# F1C200S.net
KiCad netlist of a schematic drawn in Altium Designer
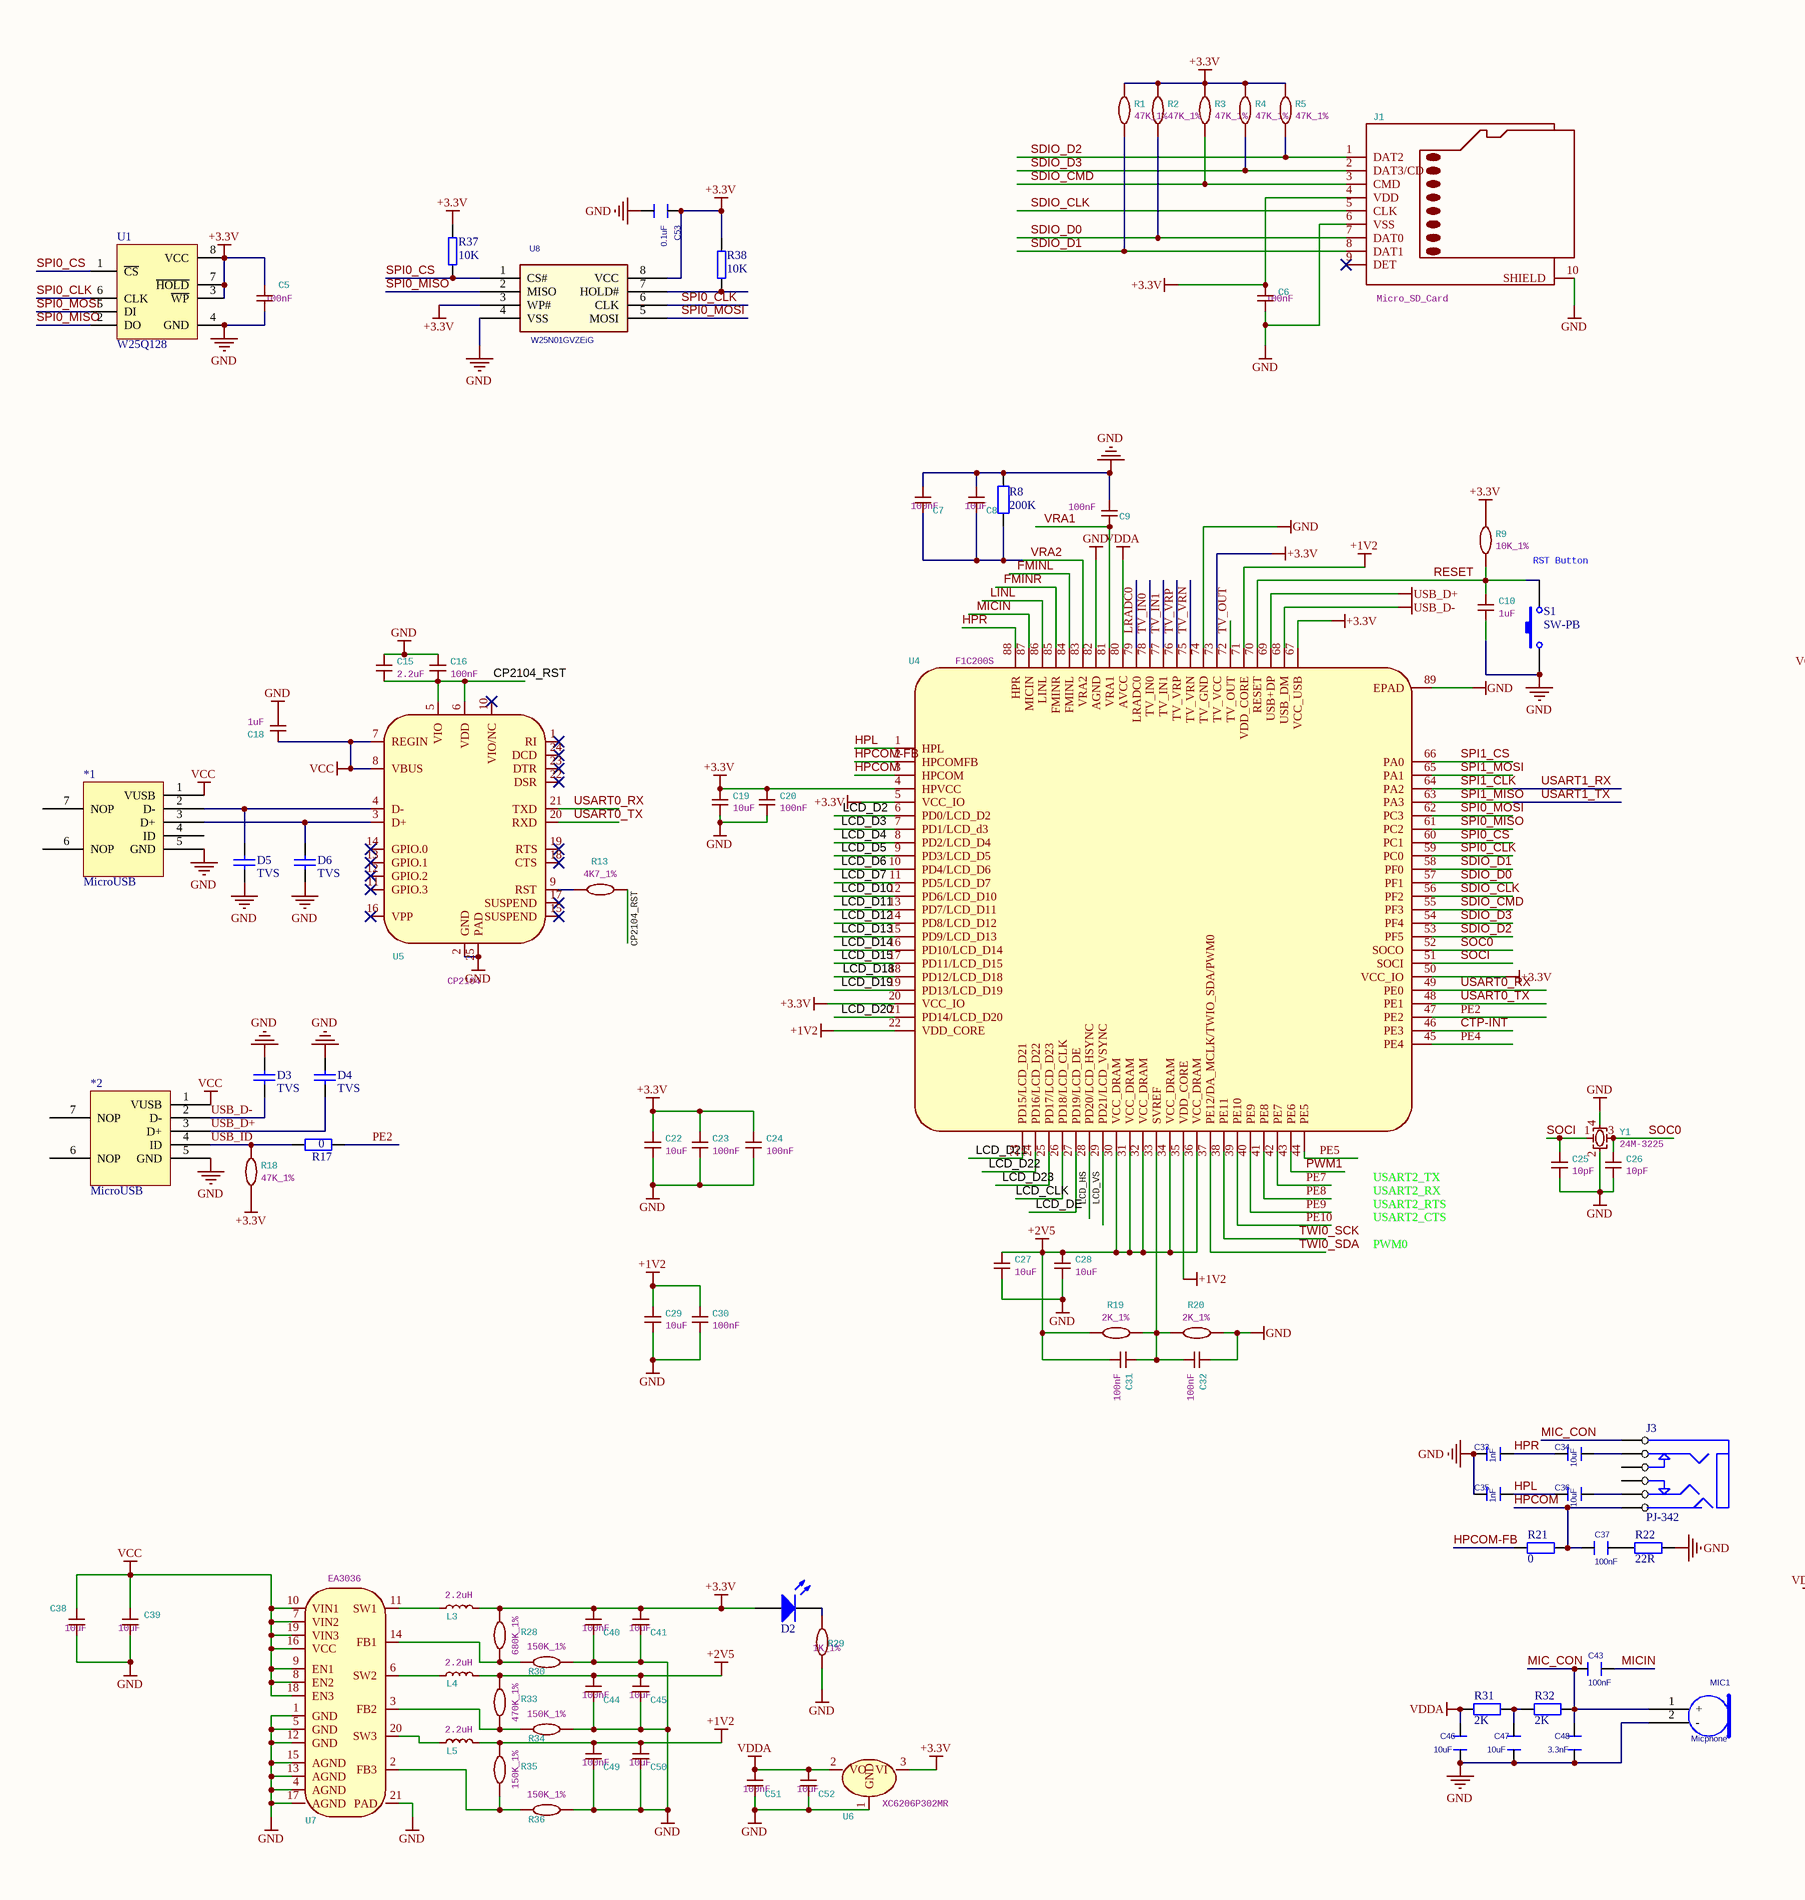
[diagram p0: F1C200S.SchDoc, left]
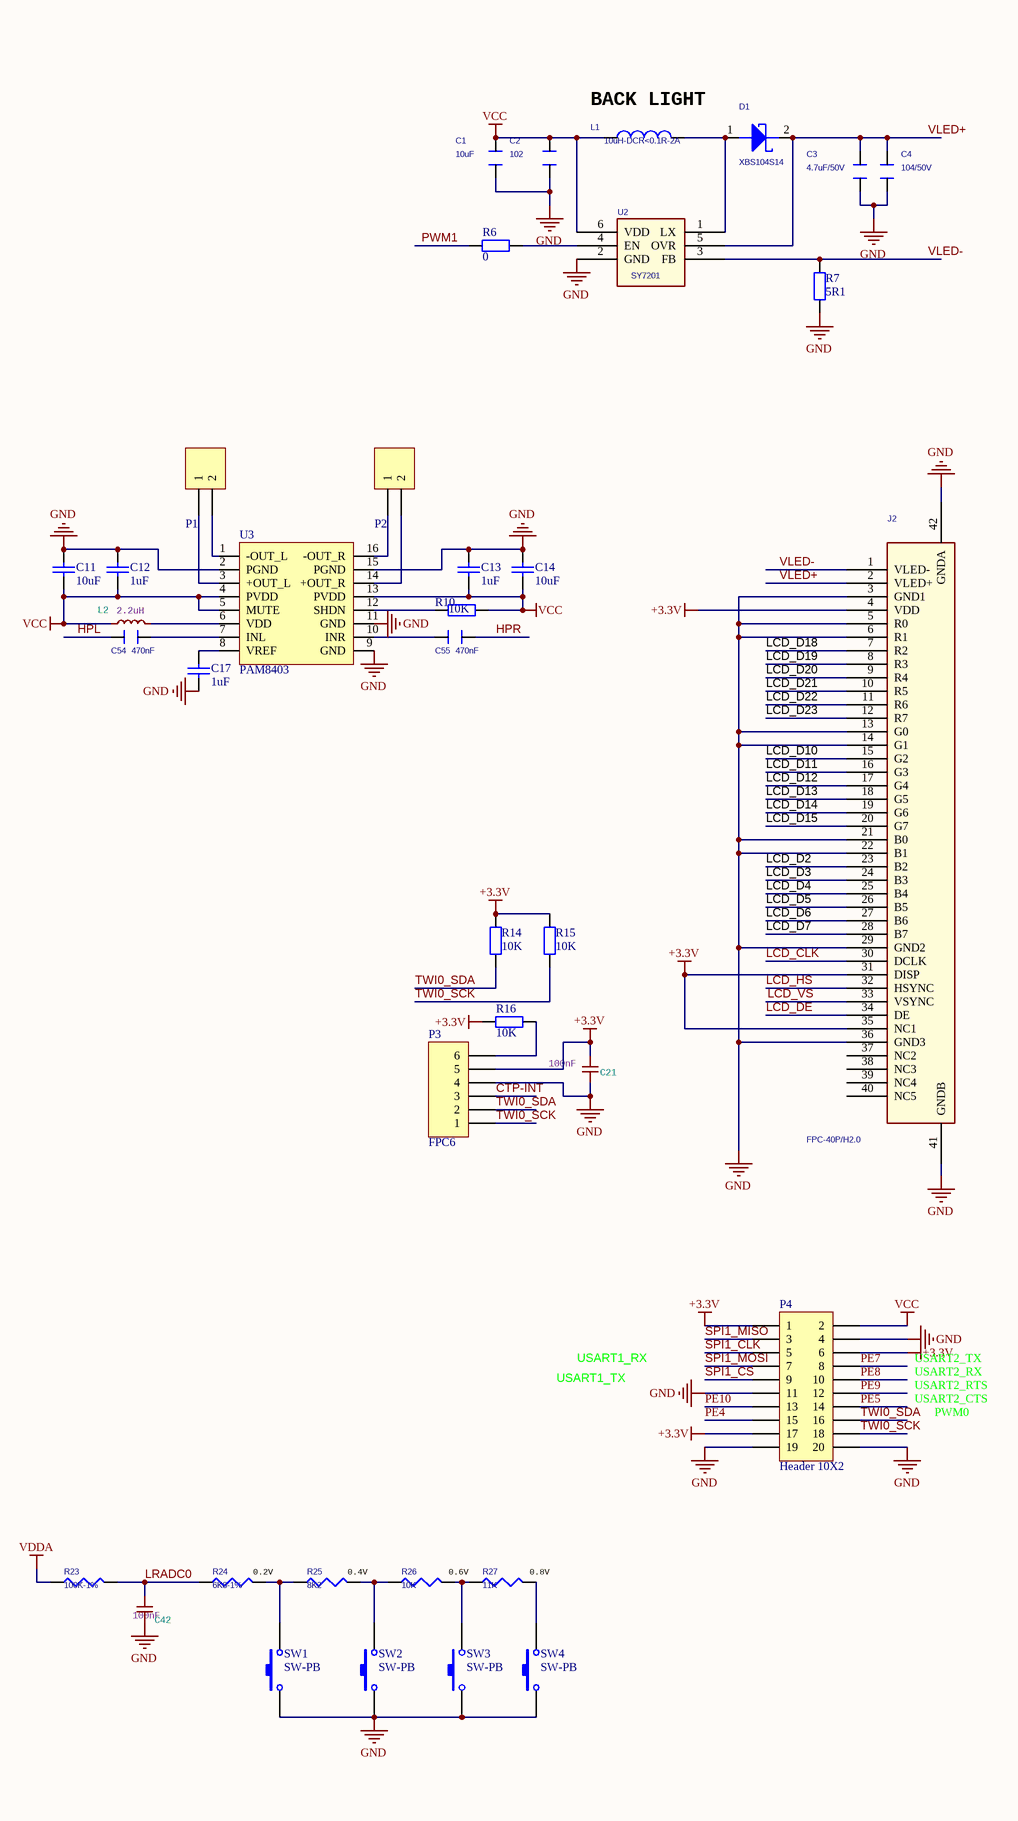
[diagram p1: F1C200S.SchDoc, right]

(export (version "E")
  (design (tool "Eeschema 10.0.6"))
  (components
    (comp (ref "*1")
      (value "MicroUSB")
      (footprint "USB_Micro - 4FP")
      (libsource (lib "USB") (part "MicroUSB"))
    )
    (comp (ref "*2")
      (value "MicroUSB")
      (footprint "USB_Micro - 4FP")
      (libsource (lib "USB") (part "MicroUSB"))
    )
    (comp (ref "C1") (value "10uF") (footprint "C0603") (libsource (lib "*") (part "CAPACITOR_0_Dup5")))
    (comp (ref "C2") (value "102") (footprint "C0603") (libsource (lib "*") (part "CAPACITOR_0_Dup5")))
    (comp (ref "C3") (value "4.7uF/50V") (footprint "C0603") (libsource (lib "*") (part "CAPACITOR_0_Dup5")))
    (comp (ref "C4") (value "104/50V") (footprint "C0603") (libsource (lib "*") (part "CAPACITOR_0_Dup5")))
    (comp (ref "C5")
      (value "03.0009_C0402_100nF")
      (footprint "C0402")
      (libsource (lib "altium-import") (part "root_0_03.0009_C0402_100nF_"))
    )
    (comp (ref "C6")
      (value "03.0009_C0402_100nF")
      (footprint "C0402")
      (libsource (lib "altium-import") (part "root_0_03.0009_C0402_100nF_"))
    )
    (comp (ref "C7")
      (value "03.0009_C0402_100nF")
      (footprint "C0402")
      (libsource (lib "altium-import") (part "root_0_mirrored_03.0009_C0402_100nF_"))
    )
    (comp (ref "C8")
      (value "03.4004_C0603_10uF")
      (footprint "C0603")
      (libsource (lib "altium-import") (part "root_0_mirrored_03.4004_C0603_10uF_"))
    )
    (comp (ref "C9")
      (value "03.0009_C0402_100nF")
      (footprint "C0402")
      (libsource (lib "altium-import") (part "root_3_03.0009_C0402_100nF_"))
    )
    (comp (ref "C10")
      (value "03.0001_C0402_1uF")
      (footprint "C0402")
      (libsource (lib "altium-import") (part "root_0_03.0001_C0402_1uF_"))
    )
    (comp (ref "C11")
      (value "10uF")
      (footprint "C0603")
      (description "无极性电容")
      (fields (field (name "Comment") "Cap") (field (name "PUBLISHER") "Altium Limited"))
      (libsource (lib "fszhang") (part "Cap"))
    )
    (comp (ref "C12")
      (value "1uF")
      (footprint "C0402")
      (description "无极性电容")
      (fields (field (name "Comment") "Cap") (field (name "PUBLISHER") "Altium Limited"))
      (libsource (lib "fszhang") (part "Cap"))
    )
    (comp (ref "C13")
      (value "1uF")
      (footprint "C0402")
      (description "无极性电容")
      (fields (field (name "Comment") "Cap") (field (name "PUBLISHER") "Altium Limited"))
      (libsource (lib "fszhang") (part "Cap"))
    )
    (comp (ref "C14")
      (value "10uF")
      (footprint "C0603")
      (description "无极性电容")
      (fields (field (name "Comment") "Cap") (field (name "PUBLISHER") "Altium Limited"))
      (libsource (lib "fszhang") (part "Cap"))
    )
    (comp (ref "C15")
      (value "03.4002_C0603_2.2uF")
      (footprint "C0402")
      (libsource (lib "altium-import") (part "root_0_03.4002_C0603_2.2uF_"))
    )
    (comp (ref "C16")
      (value "03.0009_C0402_100nF")
      (footprint "C0402")
      (libsource (lib "altium-import") (part "root_0_03.0009_C0402_100nF_"))
    )
    (comp (ref "C17")
      (value "1uF")
      (footprint "C0402")
      (description "无极性电容")
      (fields (field (name "Comment") "Cap") (field (name "PUBLISHER") "Altium Limited"))
      (libsource (lib "fszhang") (part "Cap"))
    )
    (comp (ref "C18")
      (value "03.4001_C0603_1uF")
      (footprint "C0402")
      (libsource (lib "altium-import") (part "root_0_03.4001_C0603_1uF_"))
    )
    (comp (ref "C19")
      (value "03.4004_C0603_10uF")
      (footprint "C0603")
      (libsource (lib "altium-import") (part "root_0_03.4004_C0603_10uF_"))
    )
    (comp (ref "C20")
      (value "03.0009_C0402_100nF")
      (footprint "C0402")
      (libsource (lib "altium-import") (part "root_0_03.0009_C0402_100nF_"))
    )
    (comp (ref "C21")
      (value "03.0009_C0402_100nF")
      (footprint "C0402")
      (libsource (lib "altium-import") (part "root_3_03.0009_C0402_100nF_"))
    )
    (comp (ref "C22")
      (value "03.4004_C0603_10uF")
      (footprint "C0603")
      (libsource (lib "altium-import") (part "root_0_03.4004_C0603_10uF_"))
    )
    (comp (ref "C23")
      (value "03.0009_C0402_100nF")
      (footprint "C0402")
      (libsource (lib "altium-import") (part "root_0_03.0009_C0402_100nF_"))
    )
    (comp (ref "C24")
      (value "03.0009_C0402_100nF")
      (footprint "C0402")
      (libsource (lib "altium-import") (part "root_0_03.0009_C0402_100nF_"))
    )
    (comp (ref "C25")
      (value "03.0003_C0402_10pF")
      (footprint "C0402")
      (libsource (lib "altium-import") (part "root_0_03.0003_C0402_10pF_"))
    )
    (comp (ref "C26")
      (value "03.0003_C0402_10pF")
      (footprint "C0402")
      (libsource (lib "altium-import") (part "root_0_03.0003_C0402_10pF_"))
    )
    (comp (ref "C27")
      (value "03.4004_C0603_10uF")
      (footprint "C0603")
      (libsource (lib "altium-import") (part "root_0_03.4004_C0603_10uF_"))
    )
    (comp (ref "C28")
      (value "03.4004_C0603_10uF")
      (footprint "C0603")
      (libsource (lib "altium-import") (part "root_0_03.4004_C0603_10uF_"))
    )
    (comp (ref "C29")
      (value "03.4004_C0603_10uF")
      (footprint "C0603")
      (libsource (lib "altium-import") (part "root_0_03.4004_C0603_10uF_"))
    )
    (comp (ref "C30")
      (value "03.0009_C0402_100nF")
      (footprint "C0402")
      (libsource (lib "altium-import") (part "root_0_03.0009_C0402_100nF_"))
    )
    (comp (ref "C31")
      (value "03.0009_C0402_100nF")
      (footprint "C0402")
      (libsource (lib "") (part "root_0_03.0009_C0402_100nF__1"))
    )
    (comp (ref "C32")
      (value "03.0009_C0402_100nF")
      (footprint "C0402")
      (libsource (lib "") (part "root_0_03.0009_C0402_100nF__1"))
    )
    (comp (ref "C33") (value "1nF") (footprint "C0402") (libsource (lib "*") (part "CAPACITOR_Dup3")))
    (comp (ref "C34") (value "10uF") (footprint "C0603") (libsource (lib "*") (part "CAPACITOR_Dup3")))
    (comp (ref "C35") (value "1nF") (footprint "C0402") (libsource (lib "*") (part "CAPACITOR_Dup3")))
    (comp (ref "C36") (value "10uF") (footprint "C0603") (libsource (lib "*") (part "CAPACITOR_Dup3")))
    (comp (ref "C37") (value "100nF") (footprint "C0402") (libsource (lib "*") (part "CAPACITOR_Dup3")))
    (comp (ref "C38")
      (value "03.4004_C0603_10uF")
      (footprint "C0603")
      (libsource (lib "altium-import") (part "root_0_mirrored_03.4004_C0603_10uF_"))
    )
    (comp (ref "C39")
      (value "03.4004_C0603_10uF")
      (footprint "C0603")
      (libsource (lib "altium-import") (part "root_0_mirrored_03.4004_C0603_10uF_"))
    )
    (comp (ref "C40")
      (value "03.0009_C0402_100nF")
      (footprint "C0402")
      (libsource (lib "altium-import") (part "root_0_mirrored_03.0009_C0402_100nF_"))
    )
    (comp (ref "C41")
      (value "03.4004_C0603_10uF")
      (footprint "C0603")
      (libsource (lib "altium-import") (part "root_0_mirrored_03.4004_C0603_10uF_"))
    )
    (comp (ref "C42")
      (value "03.0009_C0402_100nF")
      (footprint "C0402")
      (libsource (lib "altium-import") (part "root_0_mirrored_03.0009_C0402_100nF_"))
    )
    (comp (ref "C43") (value "100nF") (footprint "C0402") (libsource (lib "*") (part "CAPACITOR_Dup3")))
    (comp (ref "C44")
      (value "03.0009_C0402_100nF")
      (footprint "C0402")
      (libsource (lib "altium-import") (part "root_0_mirrored_03.0009_C0402_100nF_"))
    )
    (comp (ref "C45")
      (value "03.4004_C0603_10uF")
      (footprint "C0603")
      (libsource (lib "altium-import") (part "root_0_mirrored_03.4004_C0603_10uF_"))
    )
    (comp (ref "C46") (value "10uF") (footprint "C0603") (libsource (lib "*") (part "CAPACITOR_Dup3")))
    (comp (ref "C47") (value "10uF") (footprint "C0603") (libsource (lib "*") (part "CAPACITOR_Dup3")))
    (comp (ref "C48") (value "3.3nF") (footprint "C0402") (libsource (lib "*") (part "CAPACITOR_Dup3")))
    (comp (ref "C49")
      (value "03.0009_C0402_100nF")
      (footprint "C0402")
      (libsource (lib "altium-import") (part "root_0_mirrored_03.0009_C0402_100nF_"))
    )
    (comp (ref "C50")
      (value "03.4004_C0603_10uF")
      (footprint "C0603")
      (libsource (lib "altium-import") (part "root_0_mirrored_03.4004_C0603_10uF_"))
    )
    (comp (ref "C51")
      (value "03.0009_C0402_100nF")
      (footprint "C0402")
      (libsource (lib "altium-import") (part "root_0_mirrored_03.0009_C0402_100nF_"))
    )
    (comp (ref "C52")
      (value "03.4004_C0603_10uF")
      (footprint "C0603")
      (libsource (lib "altium-import") (part "root_0_mirrored_03.4004_C0603_10uF_"))
    )
    (comp (ref "C53") (value "0.1uF") (footprint "C0402") (libsource (lib "*") (part "CAPACITOR_Dup1")))
    (comp (ref "C54") (value "470nF") (footprint "C0402") (libsource (lib "*") (part "CAPACITOR_Dup1")))
    (comp (ref "C55") (value "470nF") (footprint "C0402") (libsource (lib "*") (part "CAPACITOR_Dup1")))
    (comp (ref "D1")
      (value "XBS104S14")
      (footprint "SOD123")
      (description "RoHS 1.0 Ampere Schottky Barrier Rectifiers  SOD-123")
      (libsource (lib "*") (part "DIODE SCHOTTKY_0"))
    )
    (comp (ref "D2")
      (value "LED0")
      (footprint "0603LED")
      (description "发光二极管")
      (fields (field (name "PUBLISHER") "Altium Limited"))
      (libsource (lib "fszhang") (part "LED0"))
    )
    (comp (ref "D3")
      (value "TVS")
      (footprint "C0402")
      (description "无极性电容")
      (fields (field (name "Comment") "Cap") (field (name "PUBLISHER") "Altium Limited"))
      (libsource (lib "fszhang") (part "Cap"))
    )
    (comp (ref "D4")
      (value "TVS")
      (footprint "C0402")
      (description "无极性电容")
      (fields (field (name "Comment") "Cap") (field (name "PUBLISHER") "Altium Limited"))
      (libsource (lib "fszhang") (part "Cap"))
    )
    (comp (ref "D5")
      (value "TVS")
      (footprint "C0402")
      (description "无极性电容")
      (fields (field (name "Comment") "Cap") (field (name "PUBLISHER") "Altium Limited"))
      (libsource (lib "fszhang") (part "Cap"))
    )
    (comp (ref "D6")
      (value "TVS")
      (footprint "C0402")
      (description "无极性电容")
      (fields (field (name "Comment") "Cap") (field (name "PUBLISHER") "Altium Limited"))
      (libsource (lib "fszhang") (part "Cap"))
    )
    (comp (ref "J1")
      (value "10.0001_Micro_SD_Card")
      (footprint "SDCARD-M")
      (libsource (lib "altium-import") (part "root_0_10.0001_Micro_SD_Card_"))
    )
    (comp (ref "J2")
      (value "FPC-40P/H2.0")
      (footprint "FPC0.5-40P-B")
      (libsource (lib "*") (part "LCD-LW500AC9001_0"))
    )
    (comp (ref "J3") (value "PJ-342") (footprint "PJ-342") (libsource (lib "lpi-nano-dock") (part "PJ-342")))
    (comp (ref "L1")
      (value "10uH-DCR<0.1R-2A")
      (footprint "3015")
      (description "RoHS Power Inductor 22uH 300mA H<1.8MM,CD32")
      (libsource (lib "*") (part "INDUCTOR_3"))
    )
    (comp (ref "L2")
      (value "06.0102_L2520_2.2uH")
      (footprint "3015")
      (libsource (lib "altium-import") (part "root_0_mirrored_06.0102_L2520_2.2uH_"))
    )
    (comp (ref "L3")
      (value "06.0102_L2520_2.2uH")
      (footprint "3015")
      (libsource (lib "altium-import") (part "root_0_mirrored_06.0102_L2520_2.2uH_"))
    )
    (comp (ref "L4")
      (value "06.0102_L2520_2.2uH")
      (footprint "3015")
      (libsource (lib "altium-import") (part "root_0_mirrored_06.0102_L2520_2.2uH_"))
    )
    (comp (ref "L5")
      (value "06.0102_L2520_2.2uH")
      (footprint "3015")
      (libsource (lib "altium-import") (part "root_0_mirrored_06.0102_L2520_2.2uH_"))
    )
    (comp (ref "MIC1") (value "Micphone") (footprint "MIC_6022") (libsource (lib "*") (part "Micphone_0")))
    (comp (ref "P1")
      (value "Header 2")
      (footprint "HDR2X1_A")
      (description "接插件")
      (fields (field (name "PUBLISHER") "Altium Limited"))
      (libsource (lib "fszhang") (part "Header 2"))
    )
    (comp (ref "P2")
      (value "Header 2")
      (footprint "HDR2X1_A")
      (description "接插件")
      (fields (field (name "PUBLISHER") "Altium Limited"))
      (libsource (lib "fszhang") (part "Header 2"))
    )
    (comp (ref "P3")
      (value "FPC6")
      (footprint "FPC0.5-6P-A")
      (description "接插件")
      (fields (field (name "PUBLISHER") "Altium Limited"))
      (libsource (lib "fszhang") (part "Header 6"))
    )
    (comp (ref "P4")
      (value "Header 10X2")
      (footprint "HDR2X10")
      (description "Header, 10-Pin, Dual row")
      (fields (field (name "PUBLISHER") "Altium Limited"))
      (libsource (lib "Miscellaneous Connectors") (part "Header 10X2"))
    )
    (comp (ref "R1")
      (value "02.0014_R0402_10K_1%")
      (footprint "R0402")
      (libsource (lib "altium-import") (part "root_0_02.0014_R0402_47K_1%_"))
    )
    (comp (ref "R2")
      (value "02.0014_R0402_10K_1%")
      (footprint "R0402")
      (libsource (lib "altium-import") (part "root_0_02.0014_R0402_47K_1%_"))
    )
    (comp (ref "R3")
      (value "02.0014_R0402_10K_1%")
      (footprint "R0402")
      (libsource (lib "altium-import") (part "root_0_02.0014_R0402_47K_1%_"))
    )
    (comp (ref "R4")
      (value "02.0014_R0402_10K_1%")
      (footprint "R0402")
      (libsource (lib "altium-import") (part "root_0_02.0014_R0402_47K_1%_"))
    )
    (comp (ref "R5")
      (value "02.0014_R0402_10K_1%")
      (footprint "R0402")
      (libsource (lib "altium-import") (part "root_0_02.0014_R0402_47K_1%_"))
    )
    (comp (ref "R6")
      (value "0")
      (footprint "R0402")
      (description "贴片电阻")
      (fields (field (name "Comment") "Res1") (field (name "PUBLISHER") "Altium Limited"))
      (libsource (lib "") (part "Res1_1"))
    )
    (comp (ref "R7")
      (value "5R1")
      (footprint "R0603")
      (description "贴片电阻")
      (fields (field (name "Comment") "Res1") (field (name "PUBLISHER") "Altium Limited"))
      (libsource (lib "") (part "Res1_2"))
    )
    (comp (ref "R8")
      (value "200K")
      (footprint "R0402")
      (description "贴片电阻")
      (fields (field (name "Comment") "Res1") (field (name "PUBLISHER") "Altium Limited"))
      (libsource (lib "fszhang") (part "Res1"))
    )
    (comp (ref "R9")
      (value "02.0008_R0402_10K_1%")
      (footprint "R0402")
      (libsource (lib "altium-import") (part "root_0_02.0008_R0402_10K_1%_"))
    )
    (comp (ref "R10")
      (value "10K")
      (footprint "R0402")
      (description "贴片电阻")
      (fields (field (name "Comment") "Res1") (field (name "PUBLISHER") "Altium Limited"))
      (libsource (lib "fszhang") (part "Res1"))
    )
    (comp (ref "R13")
      (value "02.0005_R0402_4K7_1%")
      (footprint "R0402")
      (libsource (lib "altium-import") (part "root_0_02.0005_R0402_4K7_1%_"))
    )
    (comp (ref "R14")
      (value "10K")
      (footprint "R0402")
      (description "贴片电阻")
      (fields (field (name "Comment") "Res1") (field (name "PUBLISHER") "Altium Limited"))
      (libsource (lib "") (part "Res1_1"))
    )
    (comp (ref "R15")
      (value "10K")
      (footprint "R0402")
      (description "贴片电阻")
      (fields (field (name "Comment") "Res1") (field (name "PUBLISHER") "Altium Limited"))
      (libsource (lib "") (part "Res1_1"))
    )
    (comp (ref "R16")
      (value "10K")
      (footprint "R0402")
      (description "贴片电阻")
      (fields (field (name "Comment") "Res1") (field (name "PUBLISHER") "Altium Limited"))
      (libsource (lib "") (part "Res1_2"))
    )
    (comp (ref "R17")
      (value "0")
      (footprint "R0402")
      (description "贴片电阻")
      (fields (field (name "Comment") "Res1") (field (name "PUBLISHER") "Altium Limited"))
      (libsource (lib "") (part "Res1_1"))
    )
    (comp (ref "R18")
      (value "02.0014_R0402_10K_1%")
      (footprint "R0402")
      (libsource (lib "altium-import") (part "root_0_02.0014_R0402_47K_1%_"))
    )
    (comp (ref "R19")
      (value "02.0026_R0402_2K_1%")
      (footprint "R0402")
      (libsource (lib "altium-import") (part "root_0_02.0026_R0402_2K_1%_"))
    )
    (comp (ref "R20")
      (value "02.0026_R0402_2K_1%")
      (footprint "R0402")
      (libsource (lib "altium-import") (part "root_0_02.0026_R0402_2K_1%_"))
    )
    (comp (ref "R21")
      (value "0")
      (footprint "R0402")
      (description "贴片电阻")
      (fields (field (name "Comment") "Res1") (field (name "PUBLISHER") "Altium Limited"))
      (libsource (lib "") (part "Res1_3"))
    )
    (comp (ref "R22")
      (value "22R")
      (footprint "R0603")
      (description "贴片电阻")
      (fields (field (name "Comment") "Res1") (field (name "PUBLISHER") "Altium Limited"))
      (libsource (lib "") (part "Res1_3"))
    )
    (comp (ref "R23") (value "100K-1%") (footprint "R0402") (libsource (lib "*") (part "R1 0805_Dup1")))
    (comp (ref "R24") (value "6K8-1%") (footprint "R0402") (libsource (lib "*") (part "R1 0805_Dup1")))
    (comp (ref "R25") (value "8K2") (footprint "R0402") (libsource (lib "*") (part "R1 0805_Dup1")))
    (comp (ref "R26") (value "10K") (footprint "R0402") (libsource (lib "*") (part "R1 0805_Dup1")))
    (comp (ref "R27") (value "11K") (footprint "R0402") (libsource (lib "*") (part "R1 0805_Dup1")))
    (comp (ref "R28")
      (value "02.0025_R0402_680K_1%")
      (footprint "R0402")
      (libsource (lib "altium-import") (part "root_0_mirrored_02.0025_R0402_680K_1%_"))
    )
    (comp (ref "R29")
      (value "02.0003_R0402_1K_1%")
      (footprint "R0402")
      (libsource (lib "altium-import") (part "root_0_mirrored_02.0003_R0402_1K_1%_"))
    )
    (comp (ref "R30")
      (value "02.0023_R0402_150K_1%")
      (footprint "R0402")
      (libsource (lib "altium-import") (part "root_0_mirrored_02.0023_R0402_150K_1%_"))
    )
    (comp (ref "R31")
      (value "2K")
      (footprint "R0402")
      (description "贴片电阻")
      (fields (field (name "Comment") "Res1") (field (name "PUBLISHER") "Altium Limited"))
      (libsource (lib "") (part "Res1_3"))
    )
    (comp (ref "R32")
      (value "2K")
      (footprint "R0402")
      (description "贴片电阻")
      (fields (field (name "Comment") "Res1") (field (name "PUBLISHER") "Altium Limited"))
      (libsource (lib "") (part "Res1_3"))
    )
    (comp (ref "R33")
      (value "02.0024_R0402_470K_1%")
      (footprint "R0402")
      (libsource (lib "altium-import") (part "root_0_mirrored_02.0024_R0402_470K_1%_"))
    )
    (comp (ref "R34")
      (value "02.0023_R0402_150K_1%")
      (footprint "R0402")
      (libsource (lib "altium-import") (part "root_0_mirrored_02.0023_R0402_150K_1%_"))
    )
    (comp (ref "R35")
      (value "02.0023_R0402_150K_1%")
      (footprint "R0402")
      (libsource (lib "") (part "root_0_mirrored_02.0023_R0402_150K_1%__1"))
    )
    (comp (ref "R36")
      (value "02.0023_R0402_150K_1%")
      (footprint "R0402")
      (libsource (lib "altium-import") (part "root_0_mirrored_02.0023_R0402_150K_1%_"))
    )
    (comp (ref "R37")
      (value "10K")
      (footprint "R0402")
      (description "Resistor")
      (libsource (lib "Renhaibo") (part "电阻Ω"))
    )
    (comp (ref "R38")
      (value "10K")
      (footprint "R0402")
      (description "Resistor")
      (libsource (lib "Renhaibo") (part "电阻Ω"))
    )
    (comp (ref "S1")
      (value "SW-PB")
      (footprint "SW_PB4_3*4*2.5")
      (description "微动开关")
      (fields (field (name "PUBLISHER") "Altium Limited"))
      (libsource (lib "fszhang") (part "SW-PB"))
    )
    (comp (ref "SW1")
      (value "SW-PB")
      (footprint "SW_PB4_3*4*2.5")
      (description "微动开关")
      (fields (field (name "PUBLISHER") "Altium Limited"))
      (libsource (lib "fszhang") (part "SW-PB"))
    )
    (comp (ref "SW2")
      (value "SW-PB")
      (footprint "SW_PB4_3*4*2.5")
      (description "微动开关")
      (fields (field (name "PUBLISHER") "Altium Limited"))
      (libsource (lib "fszhang") (part "SW-PB"))
    )
    (comp (ref "SW3")
      (value "SW-PB")
      (footprint "SW_PB4_3*4*2.5")
      (description "微动开关")
      (fields (field (name "PUBLISHER") "Altium Limited"))
      (libsource (lib "fszhang") (part "SW-PB"))
    )
    (comp (ref "SW4")
      (value "SW-PB")
      (footprint "SW_PB4_3*4*2.5")
      (description "微动开关")
      (fields (field (name "PUBLISHER") "Altium Limited"))
      (libsource (lib "fszhang") (part "SW-PB"))
    )
    (comp (ref "U1")
      (value "W25Q128")
      (footprint "SOIC8_W")
      (description "SPI FLASH")
      (libsource (lib "fszhang") (part "W25QXX"))
    )
    (comp (ref "U2") (value "SY7201") (footprint "SOT-23-6") (libsource (lib "*") (part "AP3031")))
    (comp (ref "U3") (value "PAM8403") (footprint "SOP-16") (libsource (lib "STM32 SCH") (part "PAM8403")))
    (comp (ref "U4")
      (value "08.0001_F1C200S")
      (footprint "QFN-88_EP_10X10_PITCH0.4MM")
      (libsource (lib "altium-import") (part "root_0_08.0001_F1C200S_"))
    )
    (comp (ref "U5")
      (value "09.0001_CP2104")
      (footprint "QFN-24-1EP_4X4MM_P0.5MM_EP2.6X2.6MM")
      (libsource (lib "altium-import") (part "root_0_09.0001_CP2104_"))
    )
    (comp (ref "U6")
      (value "09.0103_XC6206")
      (footprint "SOT-23")
      (libsource (lib "altium-import") (part "root_0_mirrored_09.0103_XC6206_"))
    )
    (comp (ref "U7")
      (value "09.0102_EA3036")
      (footprint "QFN-20_EP_3X3_PITCH0.4MM")
      (libsource (lib "altium-import") (part "root_0_mirrored_09.0102_EA3036_"))
    )
    (comp (ref "U8")
      (value "W25N01GVZEiG")
      (footprint "SOP-8M(PAD)")
      (libsource (lib "*") (part "SPI-NOR-SO8"))
    )
    (comp (ref "Y1")
      (value "07.0403_Crystal_24M_3225")
      (footprint "CRYSTAL-2.5X2.0")
      (libsource (lib "altium-import") (part "root_0_07.0403_Crystal_24M_3225_"))
    )
  )
  (nets
    (net (code "1") (name "+1V2") (class "Default")
      (node (ref "C29") (pin "1") (pintype "passive"))
      (node (ref "C30") (pin "1") (pintype "passive"))
      (node (ref "C49") (pin "1") (pintype "passive"))
      (node (ref "C50") (pin "1") (pintype "passive"))
      (node (ref "L5") (pin "1") (pinfunction "1_1") (pintype "passive"))
      (node (ref "R35") (pin "2") (pinfunction "2_2") (pintype "passive"))
      (node (ref "U4") (pin "22") (pinfunction "VDD_CORE_22") (pintype "passive"))
      (node (ref "U4") (pin "35") (pinfunction "VDD_CORE_35") (pintype "passive"))
      (node (ref "U4") (pin "71") (pinfunction "VDD_CORE_71") (pintype "passive"))
    )
    (net (code "2") (name "+2V5") (class "Default")
      (node (ref "C27") (pin "1") (pintype "passive"))
      (node (ref "C28") (pin "1") (pintype "passive"))
      (node (ref "C31") (pin "2") (pintype "passive"))
      (node (ref "C44") (pin "1") (pintype "passive"))
      (node (ref "C45") (pin "1") (pintype "passive"))
      (node (ref "L4") (pin "1") (pinfunction "1_1") (pintype "passive"))
      (node (ref "R19") (pin "2") (pinfunction "2_2") (pintype "passive"))
      (node (ref "R33") (pin "2") (pinfunction "2_2") (pintype "passive"))
      (node (ref "U4") (pin "30") (pinfunction "VCC_DRAM_30") (pintype "passive"))
      (node (ref "U4") (pin "31") (pinfunction "VCC_DRAM_31") (pintype "passive"))
      (node (ref "U4") (pin "32") (pinfunction "VCC_DRAM_32") (pintype "passive"))
      (node (ref "U4") (pin "34") (pinfunction "VCC_DRAM_34") (pintype "passive"))
      (node (ref "U4") (pin "36") (pinfunction "VCC_DRAM_36") (pintype "passive"))
    )
    (net (code "3") (name "+3.3V") (class "Default")
      (node (ref "C19") (pin "1") (pintype "passive"))
      (node (ref "C20") (pin "1") (pintype "passive"))
      (node (ref "C21") (pin "2") (pintype "passive"))
      (node (ref "C22") (pin "1") (pintype "passive"))
      (node (ref "C23") (pin "1") (pintype "passive"))
      (node (ref "C24") (pin "1") (pintype "passive"))
      (node (ref "C40") (pin "1") (pintype "passive"))
      (node (ref "C41") (pin "1") (pintype "passive"))
      (node (ref "C5") (pin "1") (pintype "passive"))
      (node (ref "C53") (pin "2") (pinfunction "2_2") (pintype "passive"))
      (node (ref "C6") (pin "1") (pintype "passive"))
      (node (ref "D2") (pin "1") (pinfunction "A_1") (pintype "passive"))
      (node (ref "J1") (pin "4") (pinfunction "VDD_4") (pintype "passive"))
      (node (ref "J2") (pin "31") (pinfunction "DISP_31") (pintype "passive"))
      (node (ref "J2") (pin "35") (pinfunction "NC1_35") (pintype "passive"))
      (node (ref "J2") (pin "4") (pinfunction "VDD_4") (pintype "passive"))
      (node (ref "L3") (pin "1") (pinfunction "1_1") (pintype "passive"))
      (node (ref "P3") (pin "5") (pinfunction "5_5") (pintype "passive"))
      (node (ref "P4") (pin "1") (pinfunction "1_1") (pintype "passive"))
      (node (ref "P4") (pin "17") (pinfunction "17_17") (pintype "passive"))
      (node (ref "P4") (pin "6") (pinfunction "6_6") (pintype "passive"))
      (node (ref "R1") (pin "1") (pinfunction "1_1") (pintype "passive"))
      (node (ref "R14") (pin "2") (pinfunction "2_2") (pintype "passive"))
      (node (ref "R15") (pin "2") (pinfunction "2_2") (pintype "passive"))
      (node (ref "R16") (pin "2") (pinfunction "2_2") (pintype "passive"))
      (node (ref "R18") (pin "2") (pinfunction "2_2") (pintype "passive"))
      (node (ref "R2") (pin "1") (pinfunction "1_1") (pintype "passive"))
      (node (ref "R28") (pin "2") (pinfunction "2_2") (pintype "passive"))
      (node (ref "R3") (pin "1") (pinfunction "1_1") (pintype "passive"))
      (node (ref "R37") (pin "1") (pinfunction "1_1") (pintype "passive"))
      (node (ref "R38") (pin "1") (pinfunction "1_1") (pintype "passive"))
      (node (ref "R4") (pin "1") (pinfunction "1_1") (pintype "passive"))
      (node (ref "R5") (pin "1") (pinfunction "1_1") (pintype "passive"))
      (node (ref "R9") (pin "1") (pinfunction "1_1") (pintype "passive"))
      (node (ref "U1") (pin "3") (pinfunction "~{WP}_3") (pintype "passive"))
      (node (ref "U1") (pin "7") (pinfunction "~{HOLD}_7") (pintype "passive"))
      (node (ref "U1") (pin "8") (pinfunction "VCC_8") (pintype "passive"))
      (node (ref "U4") (pin "20") (pinfunction "VCC_IO_20") (pintype "passive"))
      (node (ref "U4") (pin "4") (pinfunction "HPVCC_4") (pintype "passive"))
      (node (ref "U4") (pin "5") (pinfunction "VCC_IO_5") (pintype "passive"))
      (node (ref "U4") (pin "50") (pinfunction "VCC_IO_50") (pintype "passive"))
      (node (ref "U4") (pin "67") (pinfunction "VCC_USB_67") (pintype "passive"))
      (node (ref "U4") (pin "73") (pinfunction "TV_VCC_73") (pintype "passive"))
      (node (ref "U6") (pin "3") (pinfunction "VI_3") (pintype "passive"))
      (node (ref "U8") (pin "3") (pinfunction "WP#_3") (pintype "passive"))
      (node (ref "U8") (pin "8") (pinfunction "VCC_8") (pintype "passive"))
    )
    (net (code "4") (name "/CP2104_RST") (class "Default")
      (node (ref "C15") (pin "2") (pintype "passive"))
      (node (ref "C16") (pin "2") (pintype "passive"))
      (node (ref "R13") (pin "2") (pinfunction "2_2") (pintype "passive"))
      (node (ref "U5") (pin "5") (pinfunction "VIO_5") (pintype "passive"))
      (node (ref "U5") (pin "6") (pinfunction "VDD_6") (pintype "passive"))
    )
    (net (code "5") (name "/CTP-INT") (class "Default")
      (node (ref "P3") (pin "3") (pinfunction "3_3") (pintype "passive"))
      (node (ref "U4") (pin "46") (pinfunction "PE3_46") (pintype "passive"))
    )
    (net (code "6") (name "/FMINL") (class "Default")
      (node (ref "U4") (pin "84") (pinfunction "FMINL_84") (pintype "passive"))
    )
    (net (code "7") (name "/FMINR") (class "Default")
      (node (ref "U4") (pin "85") (pinfunction "FMINR_85") (pintype "passive"))
    )
    (net (code "8") (name "/HPCOM") (class "Default")
      (node (ref "C37") (pin "2") (pinfunction "2_2") (pintype "passive"))
      (node (ref "J3") (pin "3") (pinfunction "GND_3") (pintype "passive"))
      (node (ref "R21") (pin "1") (pinfunction "1_1") (pintype "passive"))
      (node (ref "U4") (pin "3") (pinfunction "HPCOM_3") (pintype "passive"))
    )
    (net (code "9") (name "/HPCOM-FB") (class "Default")
      (node (ref "R21") (pin "2") (pinfunction "2_2") (pintype "passive"))
      (node (ref "U4") (pin "2") (pinfunction "HPCOMFB_2") (pintype "passive"))
    )
    (net (code "10") (name "/HPL") (class "Default")
      (node (ref "C35") (pin "2") (pinfunction "2_2") (pintype "passive"))
      (node (ref "C36") (pin "1") (pinfunction "1_1") (pintype "passive"))
      (node (ref "C54") (pin "1") (pinfunction "1_1") (pintype "passive"))
      (node (ref "U4") (pin "1") (pinfunction "HPL_1") (pintype "passive"))
    )
    (net (code "11") (name "/HPR") (class "Default")
      (node (ref "C33") (pin "2") (pinfunction "2_2") (pintype "passive"))
      (node (ref "C34") (pin "1") (pinfunction "1_1") (pintype "passive"))
      (node (ref "C55") (pin "2") (pinfunction "2_2") (pintype "passive"))
      (node (ref "U4") (pin "88") (pinfunction "HPR_88") (pintype "passive"))
    )
    (net (code "12") (name "/LCD_CLK") (class "Default")
      (node (ref "J2") (pin "30") (pinfunction "DCLK_30") (pintype "passive"))
      (node (ref "U4") (pin "26") (pinfunction "PD18/LCD_CLK_26") (pintype "passive"))
    )
    (net (code "13") (name "/LCD_D2") (class "Default")
      (node (ref "J2") (pin "23") (pinfunction "B2_23") (pintype "passive"))
      (node (ref "U4") (pin "6") (pinfunction "PD0/LCD_D2_6") (pintype "passive"))
    )
    (net (code "14") (name "/LCD_D3") (class "Default")
      (node (ref "J2") (pin "24") (pinfunction "B3_24") (pintype "passive"))
      (node (ref "U4") (pin "7") (pinfunction "PD1/LCD_d3_7") (pintype "passive"))
    )
    (net (code "15") (name "/LCD_D4") (class "Default")
      (node (ref "J2") (pin "25") (pinfunction "B4_25") (pintype "passive"))
      (node (ref "U4") (pin "8") (pinfunction "PD2/LCD_D4_8") (pintype "passive"))
    )
    (net (code "16") (name "/LCD_D5") (class "Default")
      (node (ref "J2") (pin "26") (pinfunction "B5_26") (pintype "passive"))
      (node (ref "U4") (pin "9") (pinfunction "PD3/LCD_D5_9") (pintype "passive"))
    )
    (net (code "17") (name "/LCD_D6") (class "Default")
      (node (ref "J2") (pin "27") (pinfunction "B6_27") (pintype "passive"))
      (node (ref "U4") (pin "10") (pinfunction "PD4/LCD_D6_10") (pintype "passive"))
    )
    (net (code "18") (name "/LCD_D7") (class "Default")
      (node (ref "J2") (pin "28") (pinfunction "B7_28") (pintype "passive"))
      (node (ref "U4") (pin "11") (pinfunction "PD5/LCD_D7_11") (pintype "passive"))
    )
    (net (code "19") (name "/LCD_D10") (class "Default")
      (node (ref "J2") (pin "15") (pinfunction "G2_15") (pintype "passive"))
      (node (ref "U4") (pin "12") (pinfunction "PD6/LCD_D10_12") (pintype "passive"))
    )
    (net (code "20") (name "/LCD_D11") (class "Default")
      (node (ref "J2") (pin "16") (pinfunction "G3_16") (pintype "passive"))
      (node (ref "U4") (pin "13") (pinfunction "PD7/LCD_D11_13") (pintype "passive"))
    )
    (net (code "21") (name "/LCD_D12") (class "Default")
      (node (ref "J2") (pin "17") (pinfunction "G4_17") (pintype "passive"))
      (node (ref "U4") (pin "14") (pinfunction "PD8/LCD_D12_14") (pintype "passive"))
    )
    (net (code "22") (name "/LCD_D13") (class "Default")
      (node (ref "J2") (pin "18") (pinfunction "G5_18") (pintype "passive"))
      (node (ref "U4") (pin "15") (pinfunction "PD9/LCD_D13_15") (pintype "passive"))
    )
    (net (code "23") (name "/LCD_D14") (class "Default")
      (node (ref "J2") (pin "19") (pinfunction "G6_19") (pintype "passive"))
      (node (ref "U4") (pin "16") (pinfunction "PD10/LCD_D14_16") (pintype "passive"))
    )
    (net (code "24") (name "/LCD_D15") (class "Default")
      (node (ref "J2") (pin "20") (pinfunction "G7_20") (pintype "passive"))
      (node (ref "U4") (pin "17") (pinfunction "PD11/LCD_D15_17") (pintype "passive"))
    )
    (net (code "25") (name "/LCD_D18") (class "Default")
      (node (ref "J2") (pin "7") (pinfunction "R2_7") (pintype "passive"))
      (node (ref "U4") (pin "18") (pinfunction "PD12/LCD_D18_18") (pintype "passive"))
    )
    (net (code "26") (name "/LCD_D19") (class "Default")
      (node (ref "J2") (pin "8") (pinfunction "R3_8") (pintype "passive"))
      (node (ref "U4") (pin "19") (pinfunction "PD13/LCD_D19_19") (pintype "passive"))
    )
    (net (code "27") (name "/LCD_D20") (class "Default")
      (node (ref "J2") (pin "9") (pinfunction "R4_9") (pintype "passive"))
      (node (ref "U4") (pin "21") (pinfunction "PD14/LCD_D20_21") (pintype "passive"))
    )
    (net (code "28") (name "/LCD_D21") (class "Default")
      (node (ref "J2") (pin "10") (pinfunction "R5_10") (pintype "passive"))
      (node (ref "U4") (pin "23") (pinfunction "PD15/LCD_D21_23") (pintype "passive"))
    )
    (net (code "29") (name "/LCD_D22") (class "Default")
      (node (ref "J2") (pin "11") (pinfunction "R6_11") (pintype "passive"))
      (node (ref "U4") (pin "24") (pinfunction "PD16/LCD_D22_24") (pintype "passive"))
    )
    (net (code "30") (name "/LCD_D23") (class "Default")
      (node (ref "J2") (pin "12") (pinfunction "R7_12") (pintype "passive"))
      (node (ref "U4") (pin "25") (pinfunction "PD17/LCD_D23_25") (pintype "passive"))
    )
    (net (code "31") (name "/LCD_DE") (class "Default")
      (node (ref "J2") (pin "34") (pinfunction "DE_34") (pintype "passive"))
      (node (ref "U4") (pin "27") (pinfunction "PD19/LCD_DE_27") (pintype "passive"))
    )
    (net (code "32") (name "/LCD_HS") (class "Default")
      (node (ref "J2") (pin "32") (pinfunction "HSYNC_32") (pintype "passive"))
      (node (ref "U4") (pin "28") (pinfunction "PD20/LCD_HSYNC_28") (pintype "passive"))
    )
    (net (code "33") (name "/LCD_VS") (class "Default")
      (node (ref "J2") (pin "33") (pinfunction "VSYNC_33") (pintype "passive"))
      (node (ref "U4") (pin "29") (pinfunction "PD21/LCD_VSYNC_29") (pintype "passive"))
    )
    (net (code "34") (name "/LINL") (class "Default")
      (node (ref "U4") (pin "86") (pinfunction "LINL_86") (pintype "passive"))
    )
    (net (code "35") (name "/LRADC0") (class "Default")
      (node (ref "C42") (pin "1") (pintype "passive"))
      (node (ref "R23") (pin "2") (pinfunction "2_2") (pintype "passive"))
      (node (ref "R24") (pin "1") (pinfunction "1_1") (pintype "passive"))
      (node (ref "U4") (pin "79") (pinfunction "LRADC0_79") (pintype "passive"))
    )
    (net (code "36") (name "/MICIN") (class "Default")
      (node (ref "C43") (pin "1") (pinfunction "1_1") (pintype "passive"))
      (node (ref "U4") (pin "87") (pinfunction "MICIN_87") (pintype "passive"))
    )
    (net (code "37") (name "/MIC_CON") (class "Default")
      (node (ref "C43") (pin "2") (pinfunction "2_2") (pintype "passive"))
      (node (ref "C48") (pin "1") (pinfunction "1_1") (pintype "passive"))
      (node (ref "J3") (pin "2") (pinfunction "MIC_2") (pintype "passive"))
      (node (ref "MIC1") (pin "1") (pinfunction "+_1") (pintype "passive"))
      (node (ref "R32") (pin "1") (pinfunction "1_1") (pintype "passive"))
    )
    (net (code "38") (name "/PE2") (class "Default")
      (node (ref "R17") (pin "2") (pinfunction "2_2") (pintype "passive"))
      (node (ref "U4") (pin "47") (pinfunction "PE2_47") (pintype "passive"))
    )
    (net (code "39") (name "/PE4") (class "Default")
      (node (ref "P4") (pin "15") (pinfunction "15_15") (pintype "passive"))
      (node (ref "U4") (pin "45") (pinfunction "PE4_45") (pintype "passive"))
    )
    (net (code "40") (name "/PE5") (class "Default")
      (node (ref "P4") (pin "14") (pinfunction "14_14") (pintype "passive"))
      (node (ref "U4") (pin "44") (pinfunction "PE5_44") (pintype "passive"))
    )
    (net (code "41") (name "/PE7") (class "Default")
      (node (ref "P4") (pin "8") (pinfunction "8_8") (pintype "passive"))
      (node (ref "U4") (pin "42") (pinfunction "PE7_42") (pintype "passive"))
    )
    (net (code "42") (name "/PE8") (class "Default")
      (node (ref "P4") (pin "10") (pinfunction "10_10") (pintype "passive"))
      (node (ref "U4") (pin "41") (pinfunction "PE8_41") (pintype "passive"))
    )
    (net (code "43") (name "/PE9") (class "Default")
      (node (ref "P4") (pin "12") (pinfunction "12_12") (pintype "passive"))
      (node (ref "U4") (pin "40") (pinfunction "PE9_40") (pintype "passive"))
    )
    (net (code "44") (name "/PE10") (class "Default")
      (node (ref "P4") (pin "13") (pinfunction "13_13") (pintype "passive"))
      (node (ref "U4") (pin "39") (pinfunction "PE10_39") (pintype "passive"))
    )
    (net (code "46") (name "/PWM1") (class "Default")
      (node (ref "R6") (pin "1") (pinfunction "1_1") (pintype "passive"))
      (node (ref "U4") (pin "43") (pinfunction "PE6_43") (pintype "passive"))
    )
    (net (code "47") (name "/RESET") (class "Default")
      (node (ref "C10") (pin "1") (pintype "passive"))
      (node (ref "R9") (pin "2") (pinfunction "2_2") (pintype "passive"))
      (node (ref "S1") (pin "2") (pinfunction "2_2") (pintype "passive"))
      (node (ref "U4") (pin "70") (pinfunction "RESET_70") (pintype "passive"))
    )
    (net (code "48") (name "/SDIO_CLK") (class "Default")
      (node (ref "J1") (pin "5") (pinfunction "CLK_5") (pintype "passive"))
      (node (ref "U4") (pin "56") (pinfunction "PF2_56") (pintype "passive"))
    )
    (net (code "49") (name "/SDIO_CMD") (class "Default")
      (node (ref "J1") (pin "3") (pinfunction "CMD_3") (pintype "passive"))
      (node (ref "R3") (pin "2") (pinfunction "2_2") (pintype "passive"))
      (node (ref "U4") (pin "55") (pinfunction "PF3_55") (pintype "passive"))
    )
    (net (code "50") (name "/SDIO_D0") (class "Default")
      (node (ref "J1") (pin "7") (pinfunction "DAT0_7") (pintype "passive"))
      (node (ref "R2") (pin "2") (pinfunction "2_2") (pintype "passive"))
      (node (ref "U4") (pin "57") (pinfunction "PF1_57") (pintype "passive"))
    )
    (net (code "51") (name "/SDIO_D1") (class "Default")
      (node (ref "J1") (pin "8") (pinfunction "DAT1_8") (pintype "passive"))
      (node (ref "R1") (pin "2") (pinfunction "2_2") (pintype "passive"))
      (node (ref "U4") (pin "58") (pinfunction "PF0_58") (pintype "passive"))
    )
    (net (code "52") (name "/SDIO_D2") (class "Default")
      (node (ref "J1") (pin "1") (pinfunction "DAT2_1") (pintype "passive"))
      (node (ref "R5") (pin "2") (pinfunction "2_2") (pintype "passive"))
      (node (ref "U4") (pin "53") (pinfunction "PF5_53") (pintype "passive"))
    )
    (net (code "53") (name "/SDIO_D3") (class "Default")
      (node (ref "J1") (pin "2") (pinfunction "DAT3/CD_2") (pintype "passive"))
      (node (ref "R4") (pin "2") (pinfunction "2_2") (pintype "passive"))
      (node (ref "U4") (pin "54") (pinfunction "PF4_54") (pintype "passive"))
    )
    (net (code "54") (name "/SOC0") (class "Default")
      (node (ref "C26") (pin "1") (pintype "passive"))
      (node (ref "U4") (pin "52") (pinfunction "SOCO_52") (pintype "passive"))
      (node (ref "Y1") (pin "3") (pinfunction "3_3") (pintype "passive"))
    )
    (net (code "55") (name "/SOCI") (class "Default")
      (node (ref "C25") (pin "1") (pintype "passive"))
      (node (ref "U4") (pin "51") (pinfunction "SOCI_51") (pintype "passive"))
      (node (ref "Y1") (pin "1") (pinfunction "1_1") (pintype "passive"))
    )
    (net (code "56") (name "/SPI0_CLK") (class "Default")
      (node (ref "U1") (pin "6") (pinfunction "CLK_6") (pintype "passive"))
      (node (ref "U4") (pin "59") (pinfunction "PC0_59") (pintype "passive"))
      (node (ref "U8") (pin "6") (pinfunction "CLK_6") (pintype "passive"))
    )
    (net (code "57") (name "/SPI0_CS") (class "Default")
      (node (ref "R37") (pin "2") (pinfunction "2_2") (pintype "passive"))
      (node (ref "U1") (pin "1") (pinfunction "~{CS}_1") (pintype "passive"))
      (node (ref "U4") (pin "60") (pinfunction "PC1_60") (pintype "passive"))
      (node (ref "U8") (pin "1") (pinfunction "CS#_1") (pintype "passive"))
    )
    (net (code "58") (name "/SPI0_MISO") (class "Default")
      (node (ref "U1") (pin "2") (pinfunction "DO_2") (pintype "passive"))
      (node (ref "U4") (pin "61") (pinfunction "PC2_61") (pintype "passive"))
      (node (ref "U8") (pin "2") (pinfunction "MISO_2") (pintype "passive"))
    )
    (net (code "59") (name "/SPI0_MOSI") (class "Default")
      (node (ref "U1") (pin "5") (pinfunction "DI_5") (pintype "passive"))
      (node (ref "U4") (pin "62") (pinfunction "PC3_62") (pintype "passive"))
      (node (ref "U8") (pin "5") (pinfunction "MOSI_5") (pintype "passive"))
    )
    (net (code "60") (name "/SPI1_CLK") (class "Default")
      (node (ref "P4") (pin "5") (pinfunction "5_5") (pintype "passive"))
      (node (ref "U4") (pin "64") (pinfunction "PA2_64") (pintype "passive"))
    )
    (net (code "61") (name "/SPI1_CS") (class "Default")
      (node (ref "P4") (pin "9") (pinfunction "9_9") (pintype "passive"))
      (node (ref "U4") (pin "66") (pinfunction "PA0_66") (pintype "passive"))
    )
    (net (code "62") (name "/SPI1_MISO") (class "Default")
      (node (ref "P4") (pin "3") (pinfunction "3_3") (pintype "passive"))
      (node (ref "U4") (pin "63") (pinfunction "PA3_63") (pintype "passive"))
    )
    (net (code "63") (name "/SPI1_MOSI") (class "Default")
      (node (ref "P4") (pin "7") (pinfunction "7_7") (pintype "passive"))
      (node (ref "U4") (pin "65") (pinfunction "PA1_65") (pintype "passive"))
    )
    (net (code "64") (name "/TV_IN0") (class "Default")
      (node (ref "U4") (pin "78") (pinfunction "TV_IN0_78") (pintype "passive"))
    )
    (net (code "65") (name "/TV_IN1") (class "Default")
      (node (ref "U4") (pin "77") (pinfunction "TV_IN1_77") (pintype "passive"))
    )
    (net (code "66") (name "/TV_OUT") (class "Default")
      (node (ref "U4") (pin "72") (pinfunction "TV_OUT_72") (pintype "passive"))
    )
    (net (code "67") (name "/TV_VRN") (class "Default")
      (node (ref "U4") (pin "75") (pinfunction "TV_VRN_75") (pintype "passive"))
    )
    (net (code "68") (name "/TV_VRP") (class "Default")
      (node (ref "U4") (pin "76") (pinfunction "TV_VRP_76") (pintype "passive"))
    )
    (net (code "69") (name "/TWI0_SCK") (class "Default")
      (node (ref "P3") (pin "1") (pinfunction "1_1") (pintype "passive"))
      (node (ref "P4") (pin "18") (pinfunction "18_18") (pintype "passive"))
      (node (ref "R15") (pin "1") (pinfunction "1_1") (pintype "passive"))
      (node (ref "U4") (pin "38") (pinfunction "PE11_38") (pintype "passive"))
    )
    (net (code "70") (name "/TWI0_SDA") (class "Default")
      (node (ref "P3") (pin "2") (pinfunction "2_2") (pintype "passive"))
      (node (ref "P4") (pin "16") (pinfunction "16_16") (pintype "passive"))
      (node (ref "R14") (pin "1") (pinfunction "1_1") (pintype "passive"))
      (node (ref "U4") (pin "37") (pinfunction "PE12/DA_MCLK/TWIO_SDA/PWM0_37") (pintype "passive"))
    )
    (net (code "71") (name "/USART0_RX") (class "Default")
      (node (ref "U4") (pin "49") (pinfunction "PE0_49") (pintype "passive"))
      (node (ref "U5") (pin "21") (pinfunction "TXD_21") (pintype "passive"))
    )
    (net (code "72") (name "/USART0_TX") (class "Default")
      (node (ref "U4") (pin "48") (pinfunction "PE1_48") (pintype "passive"))
      (node (ref "U5") (pin "20") (pinfunction "RXD_20") (pintype "passive"))
    )
    (net (code "77") (name "/USB_ID") (class "Default")
      (node (ref "*2") (pin "4") (pinfunction "ID_4") (pintype "passive"))
      (node (ref "R17") (pin "1") (pinfunction "1_1") (pintype "passive"))
      (node (ref "R18") (pin "1") (pinfunction "1_1") (pintype "passive"))
    )
    (net (code "78") (name "/VLED+") (class "Default")
      (node (ref "C3") (pin "2") (pinfunction "2_2") (pintype "passive"))
      (node (ref "C4") (pin "2") (pinfunction "2_2") (pintype "passive"))
      (node (ref "D1") (pin "2") (pinfunction "2_2") (pintype "passive"))
      (node (ref "J2") (pin "2") (pinfunction "VLED+_2") (pintype "passive"))
      (node (ref "U2") (pin "5") (pinfunction "OVR_5") (pintype "passive"))
    )
    (net (code "79") (name "/VLED-") (class "Default")
      (node (ref "J2") (pin "1") (pinfunction "VLED-_1") (pintype "passive"))
      (node (ref "R7") (pin "1") (pinfunction "1_1") (pintype "passive"))
      (node (ref "U2") (pin "3") (pinfunction "FB_3") (pintype "passive"))
    )
    (net (code "80") (name "/VRA1") (class "Default")
      (node (ref "C9") (pin "1") (pintype "passive"))
      (node (ref "U4") (pin "81") (pinfunction "VRA1_81") (pintype "passive"))
    )
    (net (code "81") (name "/VRA2") (class "Default")
      (node (ref "C7") (pin "2") (pintype "passive"))
      (node (ref "C8") (pin "2") (pintype "passive"))
      (node (ref "R8") (pin "1") (pinfunction "1_1") (pintype "passive"))
      (node (ref "U4") (pin "83") (pinfunction "VRA2_83") (pintype "passive"))
    )
    (net (code "82") (name "GND") (class "Default")
      (node (ref "*1") (pin "5") (pinfunction "GND_5") (pintype "passive"))
      (node (ref "*2") (pin "5") (pinfunction "GND_5") (pintype "passive"))
      (node (ref "C1") (pin "1") (pinfunction "1_1") (pintype "passive"))
      (node (ref "C10") (pin "2") (pintype "passive"))
      (node (ref "C11") (pin "1") (pinfunction "1_1") (pintype "passive"))
      (node (ref "C12") (pin "1") (pinfunction "1_1") (pintype "passive"))
      (node (ref "C13") (pin "1") (pinfunction "1_1") (pintype "passive"))
      (node (ref "C14") (pin "1") (pinfunction "1_1") (pintype "passive"))
      (node (ref "C15") (pin "1") (pintype "passive"))
      (node (ref "C16") (pin "1") (pintype "passive"))
      (node (ref "C17") (pin "2") (pinfunction "2_2") (pintype "passive"))
      (node (ref "C18") (pin "2") (pintype "passive"))
      (node (ref "C19") (pin "2") (pintype "passive"))
      (node (ref "C2") (pin "1") (pinfunction "1_1") (pintype "passive"))
      (node (ref "C20") (pin "2") (pintype "passive"))
      (node (ref "C21") (pin "1") (pintype "passive"))
      (node (ref "C22") (pin "2") (pintype "passive"))
      (node (ref "C23") (pin "2") (pintype "passive"))
      (node (ref "C24") (pin "2") (pintype "passive"))
      (node (ref "C25") (pin "2") (pintype "passive"))
      (node (ref "C26") (pin "2") (pintype "passive"))
      (node (ref "C27") (pin "2") (pintype "passive"))
      (node (ref "C28") (pin "2") (pintype "passive"))
      (node (ref "C29") (pin "2") (pintype "passive"))
      (node (ref "C3") (pin "1") (pinfunction "1_1") (pintype "passive"))
      (node (ref "C30") (pin "2") (pintype "passive"))
      (node (ref "C32") (pin "1") (pintype "passive"))
      (node (ref "C33") (pin "1") (pinfunction "1_1") (pintype "passive"))
      (node (ref "C35") (pin "1") (pinfunction "1_1") (pintype "passive"))
      (node (ref "C38") (pin "2") (pintype "passive"))
      (node (ref "C39") (pin "2") (pintype "passive"))
      (node (ref "C4") (pin "1") (pinfunction "1_1") (pintype "passive"))
      (node (ref "C40") (pin "2") (pintype "passive"))
      (node (ref "C41") (pin "2") (pintype "passive"))
      (node (ref "C42") (pin "2") (pintype "passive"))
      (node (ref "C44") (pin "2") (pintype "passive"))
      (node (ref "C45") (pin "2") (pintype "passive"))
      (node (ref "C46") (pin "2") (pinfunction "2_2") (pintype "passive"))
      (node (ref "C47") (pin "2") (pinfunction "2_2") (pintype "passive"))
      (node (ref "C48") (pin "2") (pinfunction "2_2") (pintype "passive"))
      (node (ref "C49") (pin "2") (pintype "passive"))
      (node (ref "C5") (pin "2") (pintype "passive"))
      (node (ref "C50") (pin "2") (pintype "passive"))
      (node (ref "C51") (pin "2") (pintype "passive"))
      (node (ref "C52") (pin "2") (pintype "passive"))
      (node (ref "C53") (pin "1") (pinfunction "1_1") (pintype "passive"))
      (node (ref "C6") (pin "2") (pintype "passive"))
      (node (ref "C7") (pin "1") (pintype "passive"))
      (node (ref "C8") (pin "1") (pintype "passive"))
      (node (ref "C9") (pin "2") (pintype "passive"))
      (node (ref "D3") (pin "2") (pinfunction "2_2") (pintype "passive"))
      (node (ref "D4") (pin "2") (pinfunction "2_2") (pintype "passive"))
      (node (ref "D5") (pin "1") (pinfunction "1_1") (pintype "passive"))
      (node (ref "D6") (pin "1") (pinfunction "1_1") (pintype "passive"))
      (node (ref "J1") (pin "10") (pinfunction "SHIELD_10") (pintype "passive"))
      (node (ref "J1") (pin "6") (pinfunction "VSS_6") (pintype "passive"))
      (node (ref "J2") (pin "13") (pinfunction "G0_13") (pintype "passive"))
      (node (ref "J2") (pin "14") (pinfunction "G1_14") (pintype "passive"))
      (node (ref "J2") (pin "21") (pinfunction "B0_21") (pintype "passive"))
      (node (ref "J2") (pin "22") (pinfunction "B1_22") (pintype "passive"))
      (node (ref "J2") (pin "29") (pinfunction "GND2_29") (pintype "passive"))
      (node (ref "J2") (pin "3") (pinfunction "GND1_3") (pintype "passive"))
      (node (ref "J2") (pin "36") (pinfunction "GND3_36") (pintype "passive"))
      (node (ref "J2") (pin "41") (pinfunction "GNDB_41") (pintype "passive"))
      (node (ref "J2") (pin "42") (pinfunction "GNDA_42") (pintype "passive"))
      (node (ref "J2") (pin "5") (pinfunction "R0_5") (pintype "passive"))
      (node (ref "J2") (pin "6") (pinfunction "R1_6") (pintype "passive"))
      (node (ref "MIC1") (pin "2") (pinfunction "-_2") (pintype "passive"))
      (node (ref "P3") (pin "4") (pinfunction "4_4") (pintype "passive"))
      (node (ref "P4") (pin "11") (pinfunction "11_11") (pintype "passive"))
      (node (ref "P4") (pin "19") (pinfunction "19_19") (pintype "passive"))
      (node (ref "P4") (pin "20") (pinfunction "20_20") (pintype "passive"))
      (node (ref "P4") (pin "4") (pinfunction "4_4") (pintype "passive"))
      (node (ref "R20") (pin "1") (pinfunction "1_1") (pintype "passive"))
      (node (ref "R22") (pin "1") (pinfunction "1_1") (pintype "passive"))
      (node (ref "R29") (pin "2") (pinfunction "2_2") (pintype "passive"))
      (node (ref "R30") (pin "1") (pinfunction "1_1") (pintype "passive"))
      (node (ref "R34") (pin "1") (pinfunction "1_1") (pintype "passive"))
      (node (ref "R36") (pin "1") (pinfunction "1_1") (pintype "passive"))
      (node (ref "R7") (pin "2") (pinfunction "2_2") (pintype "passive"))
      (node (ref "R8") (pin "2") (pinfunction "2_2") (pintype "passive"))
      (node (ref "S1") (pin "1") (pinfunction "1_1") (pintype "passive"))
      (node (ref "SW1") (pin "1") (pinfunction "1_1") (pintype "passive"))
      (node (ref "SW2") (pin "1") (pinfunction "1_1") (pintype "passive"))
      (node (ref "SW3") (pin "1") (pinfunction "1_1") (pintype "passive"))
      (node (ref "SW4") (pin "1") (pinfunction "1_1") (pintype "passive"))
      (node (ref "U1") (pin "4") (pinfunction "GND_4") (pintype "passive"))
      (node (ref "U2") (pin "2") (pinfunction "GND_2") (pintype "passive"))
      (node (ref "U3") (pin "11") (pinfunction "GND_11") (pintype "passive"))
      (node (ref "U3") (pin "15") (pinfunction "PGND_15") (pintype "passive"))
      (node (ref "U3") (pin "2") (pinfunction "PGND_2") (pintype "passive"))
      (node (ref "U3") (pin "9") (pinfunction "GND_9") (pintype "passive"))
      (node (ref "U4") (pin "74") (pinfunction "TV_GND_74") (pintype "passive"))
      (node (ref "U4") (pin "82") (pinfunction "AGND_82") (pintype "passive"))
      (node (ref "U4") (pin "89") (pinfunction "EPAD_89") (pintype "passive"))
      (node (ref "U5") (pin "2") (pinfunction "GND_2") (pintype "passive"))
      (node (ref "U5") (pin "25") (pinfunction "PAD_25") (pintype "passive"))
      (node (ref "U6") (pin "1") (pinfunction "GND_1") (pintype "passive"))
      (node (ref "U7") (pin "1") (pinfunction "GND_1") (pintype "passive"))
      (node (ref "U7") (pin "12") (pinfunction "GND_12") (pintype "passive"))
      (node (ref "U7") (pin "13") (pinfunction "AGND_13") (pintype "passive"))
      (node (ref "U7") (pin "15") (pinfunction "AGND_15") (pintype "passive"))
      (node (ref "U7") (pin "17") (pinfunction "AGND_17") (pintype "passive"))
      (node (ref "U7") (pin "21") (pinfunction "PAD_21") (pintype "passive"))
      (node (ref "U7") (pin "4") (pinfunction "AGND_4") (pintype "passive"))
      (node (ref "U7") (pin "5") (pinfunction "GND_5") (pintype "passive"))
      (node (ref "U8") (pin "4") (pinfunction "VSS_4") (pintype "passive"))
      (node (ref "Y1") (pin "2") (pinfunction "2_2") (pintype "passive"))
      (node (ref "Y1") (pin "4") (pinfunction "4_4") (pintype "passive"))
    )
    (net (code "83") (name "Net-(*1-D+)") (class "Default")
      (node (ref "*1") (pin "3") (pinfunction "D+_3") (pintype "passive"))
      (node (ref "D6") (pin "2") (pinfunction "2_2") (pintype "passive"))
      (node (ref "U5") (pin "3") (pinfunction "D+_3") (pintype "passive"))
    )
    (net (code "84") (name "Net-(*1-D-)") (class "Default")
      (node (ref "*1") (pin "2") (pinfunction "D-_2") (pintype "passive"))
      (node (ref "D5") (pin "2") (pinfunction "2_2") (pintype "passive"))
      (node (ref "U5") (pin "4") (pinfunction "D-_4") (pintype "passive"))
    )
    (net (code "85") (name "Net-(C37-Pad1)") (class "Default")
      (node (ref "C37") (pin "1") (pinfunction "1_1") (pintype "passive"))
      (node (ref "R22") (pin "2") (pinfunction "2_2") (pintype "passive"))
    )
    (net (code "86") (name "Net-(C47-Pad1)") (class "Default")
      (node (ref "C47") (pin "1") (pinfunction "1_1") (pintype "passive"))
      (node (ref "R31") (pin "1") (pinfunction "1_1") (pintype "passive"))
      (node (ref "R32") (pin "2") (pinfunction "2_2") (pintype "passive"))
    )
    (net (code "87") (name "Net-(D2-K)") (class "Default")
      (node (ref "D2") (pin "2") (pinfunction "K_2") (pintype "passive"))
      (node (ref "R29") (pin "1") (pinfunction "1_1") (pintype "passive"))
    )
    (net (code "88") (name "Net-(J3-L)") (class "Default")
      (node (ref "C36") (pin "2") (pinfunction "2_2") (pintype "passive"))
      (node (ref "J3") (pin "6") (pinfunction "L_6") (pintype "passive"))
    )
    (net (code "89") (name "Net-(J3-R)") (class "Default")
      (node (ref "C34") (pin "2") (pinfunction "2_2") (pintype "passive"))
      (node (ref "J3") (pin "4") (pinfunction "R_4") (pintype "passive"))
    )
    (net (code "90") (name "Net-(P3-Pad6)") (class "Default")
      (node (ref "P3") (pin "6") (pinfunction "6_6") (pintype "passive"))
      (node (ref "R16") (pin "1") (pinfunction "1_1") (pintype "passive"))
    )
    (net (code "91") (name "Net-(R24-Pad2)") (class "Default")
      (node (ref "R24") (pin "2") (pinfunction "2_2") (pintype "passive"))
      (node (ref "R25") (pin "1") (pinfunction "1_1") (pintype "passive"))
      (node (ref "SW1") (pin "2") (pinfunction "2_2") (pintype "passive"))
    )
    (net (code "92") (name "Net-(R25-Pad2)") (class "Default")
      (node (ref "R25") (pin "2") (pinfunction "2_2") (pintype "passive"))
      (node (ref "R26") (pin "1") (pinfunction "1_1") (pintype "passive"))
      (node (ref "SW2") (pin "2") (pinfunction "2_2") (pintype "passive"))
    )
    (net (code "93") (name "Net-(R26-Pad2)") (class "Default")
      (node (ref "R26") (pin "2") (pinfunction "2_2") (pintype "passive"))
      (node (ref "R27") (pin "1") (pinfunction "1_1") (pintype "passive"))
      (node (ref "SW3") (pin "2") (pinfunction "2_2") (pintype "passive"))
    )
    (net (code "94") (name "Net-(R27-Pad2)") (class "Default")
      (node (ref "R27") (pin "2") (pinfunction "2_2") (pintype "passive"))
      (node (ref "SW4") (pin "2") (pinfunction "2_2") (pintype "passive"))
    )
    (net (code "95") (name "Net-(U2-EN)") (class "Default")
      (node (ref "R6") (pin "2") (pinfunction "2_2") (pintype "passive"))
      (node (ref "U2") (pin "4") (pinfunction "EN_4") (pintype "passive"))
    )
    (net (code "96") (name "Net-(U2-LX)") (class "Default")
      (node (ref "D1") (pin "1") (pinfunction "1_1") (pintype "passive"))
      (node (ref "L1") (pin "2") (pinfunction "2_2") (pintype "passive"))
      (node (ref "U2") (pin "1") (pinfunction "LX_1") (pintype "passive"))
    )
    (net (code "97") (name "Net-(U3-+OUT_L)") (class "Default")
      (node (ref "P1") (pin "1") (pinfunction "1_1") (pintype "passive"))
      (node (ref "U3") (pin "3") (pinfunction "+OUT_L_3") (pintype "passive"))
    )
    (net (code "98") (name "Net-(U3-+OUT_R)") (class "Default")
      (node (ref "P2") (pin "2") (pinfunction "2_2") (pintype "passive"))
      (node (ref "U3") (pin "14") (pinfunction "+OUT_R_14") (pintype "passive"))
    )
    (net (code "99") (name "Net-(U3--OUT_L)") (class "Default")
      (node (ref "P1") (pin "2") (pinfunction "2_2") (pintype "passive"))
      (node (ref "U3") (pin "1") (pinfunction "-OUT_L_1") (pintype "passive"))
    )
    (net (code "100") (name "Net-(U3--OUT_R)") (class "Default")
      (node (ref "P2") (pin "1") (pinfunction "1_1") (pintype "passive"))
      (node (ref "U3") (pin "16") (pinfunction "-OUT_R_16") (pintype "passive"))
    )
    (net (code "101") (name "Net-(U3-INL)") (class "Default")
      (node (ref "C54") (pin "2") (pinfunction "2_2") (pintype "passive"))
      (node (ref "U3") (pin "7") (pinfunction "INL_7") (pintype "passive"))
    )
    (net (code "102") (name "Net-(U3-INR)") (class "Default")
      (node (ref "C55") (pin "1") (pinfunction "1_1") (pintype "passive"))
      (node (ref "U3") (pin "10") (pinfunction "INR_10") (pintype "passive"))
    )
    (net (code "103") (name "Net-(U3-SHDN)") (class "Default")
      (node (ref "R10") (pin "1") (pinfunction "1_1") (pintype "passive"))
      (node (ref "U3") (pin "12") (pinfunction "SHDN_12") (pintype "passive"))
    )
    (net (code "104") (name "Net-(U3-VDD)") (class "Default")
      (node (ref "L2") (pin "1") (pinfunction "1_1") (pintype "passive"))
      (node (ref "U3") (pin "6") (pinfunction "VDD_6") (pintype "passive"))
    )
    (net (code "105") (name "Net-(U3-VREF)") (class "Default")
      (node (ref "C17") (pin "1") (pinfunction "1_1") (pintype "passive"))
      (node (ref "U3") (pin "8") (pinfunction "VREF_8") (pintype "passive"))
    )
    (net (code "106") (name "Net-(U4-SVREF)") (class "Default")
      (node (ref "C31") (pin "1") (pintype "passive"))
      (node (ref "C32") (pin "2") (pintype "passive"))
      (node (ref "R19") (pin "1") (pinfunction "1_1") (pintype "passive"))
      (node (ref "R20") (pin "2") (pinfunction "2_2") (pintype "passive"))
      (node (ref "U4") (pin "33") (pinfunction "SVREF_33") (pintype "passive"))
    )
    (net (code "107") (name "Net-(U5-RST)") (class "Default")
      (node (ref "R13") (pin "1") (pinfunction "1_1") (pintype "passive"))
      (node (ref "U5") (pin "9") (pinfunction "RST_9") (pintype "passive"))
    )
    (net (code "108") (name "Net-(U7-FB1)") (class "Default")
      (node (ref "R28") (pin "1") (pinfunction "1_1") (pintype "passive"))
      (node (ref "R30") (pin "2") (pinfunction "2_2") (pintype "passive"))
      (node (ref "U7") (pin "14") (pinfunction "FB1_14") (pintype "passive"))
    )
    (net (code "109") (name "Net-(U7-FB2)") (class "Default")
      (node (ref "R33") (pin "1") (pinfunction "1_1") (pintype "passive"))
      (node (ref "R34") (pin "2") (pinfunction "2_2") (pintype "passive"))
      (node (ref "U7") (pin "3") (pinfunction "FB2_3") (pintype "passive"))
    )
    (net (code "110") (name "Net-(U7-FB3)") (class "Default")
      (node (ref "R35") (pin "1") (pinfunction "1_1") (pintype "passive"))
      (node (ref "R36") (pin "2") (pinfunction "2_2") (pintype "passive"))
      (node (ref "U7") (pin "2") (pinfunction "FB3_2") (pintype "passive"))
    )
    (net (code "111") (name "Net-(U7-SW1)") (class "Default")
      (node (ref "L3") (pin "2") (pinfunction "2_2") (pintype "passive"))
      (node (ref "U7") (pin "11") (pinfunction "SW1_11") (pintype "passive"))
    )
    (net (code "112") (name "Net-(U7-SW2)") (class "Default")
      (node (ref "L4") (pin "2") (pinfunction "2_2") (pintype "passive"))
      (node (ref "U7") (pin "6") (pinfunction "SW2_6") (pintype "passive"))
    )
    (net (code "113") (name "Net-(U7-SW3)") (class "Default")
      (node (ref "L5") (pin "2") (pinfunction "2_2") (pintype "passive"))
      (node (ref "U7") (pin "20") (pinfunction "SW3_20") (pintype "passive"))
    )
    (net (code "114") (name "Net-(U8-HOLD#)") (class "Default")
      (node (ref "R38") (pin "2") (pinfunction "2_2") (pintype "passive"))
      (node (ref "U8") (pin "7") (pinfunction "HOLD#_7") (pintype "passive"))
    )
    (net (code "115") (name "USB_D+") (class "Default")
      (node (ref "*2") (pin "3") (pinfunction "D+_3") (pintype "passive"))
      (node (ref "D4") (pin "1") (pinfunction "1_1") (pintype "passive"))
      (node (ref "U4") (pin "69") (pinfunction "USB+DP_69") (pintype "passive"))
    )
    (net (code "116") (name "USB_D-") (class "Default")
      (node (ref "*2") (pin "2") (pinfunction "D-_2") (pintype "passive"))
      (node (ref "D3") (pin "1") (pinfunction "1_1") (pintype "passive"))
      (node (ref "U4") (pin "68") (pinfunction "USB_DM_68") (pintype "passive"))
    )
    (net (code "117") (name "VCC") (class "Default")
      (node (ref "*1") (pin "1") (pinfunction "VUSB_1") (pintype "passive"))
      (node (ref "*2") (pin "1") (pinfunction "VUSB_1") (pintype "passive"))
      (node (ref "C1") (pin "2") (pinfunction "2_2") (pintype "passive"))
      (node (ref "C11") (pin "2") (pinfunction "2_2") (pintype "passive"))
      (node (ref "C12") (pin "2") (pinfunction "2_2") (pintype "passive"))
      (node (ref "C13") (pin "2") (pinfunction "2_2") (pintype "passive"))
      (node (ref "C14") (pin "2") (pinfunction "2_2") (pintype "passive"))
      (node (ref "C18") (pin "1") (pintype "passive"))
      (node (ref "C2") (pin "2") (pinfunction "2_2") (pintype "passive"))
      (node (ref "C38") (pin "1") (pintype "passive"))
      (node (ref "C39") (pin "1") (pintype "passive"))
      (node (ref "L1") (pin "1") (pinfunction "1_1") (pintype "passive"))
      (node (ref "L2") (pin "2") (pinfunction "2_2") (pintype "passive"))
      (node (ref "P4") (pin "2") (pinfunction "2_2") (pintype "passive"))
      (node (ref "R10") (pin "2") (pinfunction "2_2") (pintype "passive"))
      (node (ref "U2") (pin "6") (pinfunction "VDD_6") (pintype "passive"))
      (node (ref "U3") (pin "13") (pinfunction "PVDD_13") (pintype "passive"))
      (node (ref "U3") (pin "4") (pinfunction "PVDD_4") (pintype "passive"))
      (node (ref "U3") (pin "5") (pinfunction "MUTE_5") (pintype "passive"))
      (node (ref "U5") (pin "7") (pinfunction "REGIN_7") (pintype "passive"))
      (node (ref "U5") (pin "8") (pinfunction "VBUS_8") (pintype "passive"))
      (node (ref "U7") (pin "10") (pinfunction "VIN1_10") (pintype "passive"))
      (node (ref "U7") (pin "16") (pinfunction "VCC_16") (pintype "passive"))
      (node (ref "U7") (pin "18") (pinfunction "EN3_18") (pintype "passive"))
      (node (ref "U7") (pin "19") (pinfunction "VIN3_19") (pintype "passive"))
      (node (ref "U7") (pin "7") (pinfunction "VIN2_7") (pintype "passive"))
      (node (ref "U7") (pin "8") (pinfunction "EN2_8") (pintype "passive"))
      (node (ref "U7") (pin "9") (pinfunction "EN1_9") (pintype "passive"))
    )
    (net (code "118") (name "VDDA") (class "Default")
      (node (ref "C46") (pin "1") (pinfunction "1_1") (pintype "passive"))
      (node (ref "C51") (pin "1") (pintype "passive"))
      (node (ref "C52") (pin "1") (pintype "passive"))
      (node (ref "R23") (pin "1") (pinfunction "1_1") (pintype "passive"))
      (node (ref "R31") (pin "2") (pinfunction "2_2") (pintype "passive"))
      (node (ref "U4") (pin "80") (pinfunction "AVCC_80") (pintype "passive"))
      (node (ref "U6") (pin "2") (pinfunction "VO_2") (pintype "passive"))
    )
    (net (code "119") (name "unconnected-(*1-ID-Pad4)") (class "Default")
      (node (ref "*1") (pin "4") (pinfunction "ID_4") (pintype "passive"))
    )
    (net (code "120") (name "unconnected-(*1-NOP-Pad6)") (class "Default")
      (node (ref "*1") (pin "6") (pinfunction "NOP_6") (pintype "passive"))
    )
    (net (code "121") (name "unconnected-(*1-NOP-Pad7)") (class "Default")
      (node (ref "*1") (pin "7") (pinfunction "NOP_7") (pintype "passive"))
    )
    (net (code "122") (name "unconnected-(*2-NOP-Pad6)") (class "Default")
      (node (ref "*2") (pin "6") (pinfunction "NOP_6") (pintype "passive"))
    )
    (net (code "123") (name "unconnected-(*2-NOP-Pad7)") (class "Default")
      (node (ref "*2") (pin "7") (pinfunction "NOP_7") (pintype "passive"))
    )
    (net (code "124") (name "unconnected-(J1-DET-Pad9)") (class "Default")
      (node (ref "J1") (pin "9") (pinfunction "DET_9") (pintype "passive+no_connect"))
    )
    (net (code "125") (name "unconnected-(J2-NC2-Pad37)") (class "Default")
      (node (ref "J2") (pin "37") (pinfunction "NC2_37") (pintype "passive"))
    )
    (net (code "126") (name "unconnected-(J2-NC3-Pad38)") (class "Default")
      (node (ref "J2") (pin "38") (pinfunction "NC3_38") (pintype "passive"))
    )
    (net (code "127") (name "unconnected-(J2-NC4-Pad39)") (class "Default")
      (node (ref "J2") (pin "39") (pinfunction "NC4_39") (pintype "passive"))
    )
    (net (code "128") (name "unconnected-(J2-NC5-Pad40)") (class "Default")
      (node (ref "J2") (pin "40") (pinfunction "NC5_40") (pintype "passive"))
    )
    (net (code "129") (name "unconnected-(J3-L_DET-Pad7)") (class "Default")
      (node (ref "J3") (pin "7") (pinfunction "L_DET_7") (pintype "passive"))
    )
    (net (code "130") (name "unconnected-(J3-R_DET-Pad5)") (class "Default")
      (node (ref "J3") (pin "5") (pinfunction "R_DET_5") (pintype "passive"))
    )
    (net (code "131") (name "unconnected-(U5-CTS-Pad18)") (class "Default")
      (node (ref "U5") (pin "18") (pinfunction "CTS_18") (pintype "passive+no_connect"))
    )
    (net (code "132") (name "unconnected-(U5-DCD-Pad24)") (class "Default")
      (node (ref "U5") (pin "24") (pinfunction "DCD_24") (pintype "passive+no_connect"))
    )
    (net (code "133") (name "unconnected-(U5-DSR-Pad22)") (class "Default")
      (node (ref "U5") (pin "22") (pinfunction "DSR_22") (pintype "passive+no_connect"))
    )
    (net (code "134") (name "unconnected-(U5-DTR-Pad23)") (class "Default")
      (node (ref "U5") (pin "23") (pinfunction "DTR_23") (pintype "passive+no_connect"))
    )
    (net (code "135") (name "unconnected-(U5-GPIO.0-Pad14)") (class "Default")
      (node (ref "U5") (pin "14") (pinfunction "GPIO.0_14") (pintype "passive+no_connect"))
    )
    (net (code "136") (name "unconnected-(U5-GPIO.1-Pad13)") (class "Default")
      (node (ref "U5") (pin "13") (pinfunction "GPIO.1_13") (pintype "passive+no_connect"))
    )
    (net (code "137") (name "unconnected-(U5-GPIO.2-Pad12)") (class "Default")
      (node (ref "U5") (pin "12") (pinfunction "GPIO.2_12") (pintype "passive+no_connect"))
    )
    (net (code "138") (name "unconnected-(U5-GPIO.3-Pad11)") (class "Default")
      (node (ref "U5") (pin "11") (pinfunction "GPIO.3_11") (pintype "passive+no_connect"))
    )
    (net (code "139") (name "unconnected-(U5-RI-Pad1)") (class "Default")
      (node (ref "U5") (pin "1") (pinfunction "RI_1") (pintype "passive+no_connect"))
    )
    (net (code "140") (name "unconnected-(U5-RTS-Pad19)") (class "Default")
      (node (ref "U5") (pin "19") (pinfunction "RTS_19") (pintype "passive+no_connect"))
    )
    (net (code "141") (name "unconnected-(U5-SUSPEND-Pad15)") (class "Default")
      (node (ref "U5") (pin "15") (pinfunction "SUSPEND_15") (pintype "passive+no_connect"))
    )
    (net (code "142") (name "unconnected-(U5-SUSPEND-Pad17)") (class "Default")
      (node (ref "U5") (pin "17") (pinfunction "SUSPEND_17") (pintype "passive+no_connect"))
    )
    (net (code "143") (name "unconnected-(U5-VIO{slash}NC-Pad10)") (class "Default")
      (node (ref "U5") (pin "10") (pinfunction "VIO/NC_10") (pintype "passive+no_connect"))
    )
    (net (code "144") (name "unconnected-(U5-VPP-Pad16)") (class "Default")
      (node (ref "U5") (pin "16") (pinfunction "VPP_16") (pintype "passive+no_connect"))
    )
  )
)
